# CM5_GPIO.net
KiCad netlist of a schematic drawn in Altium Designer
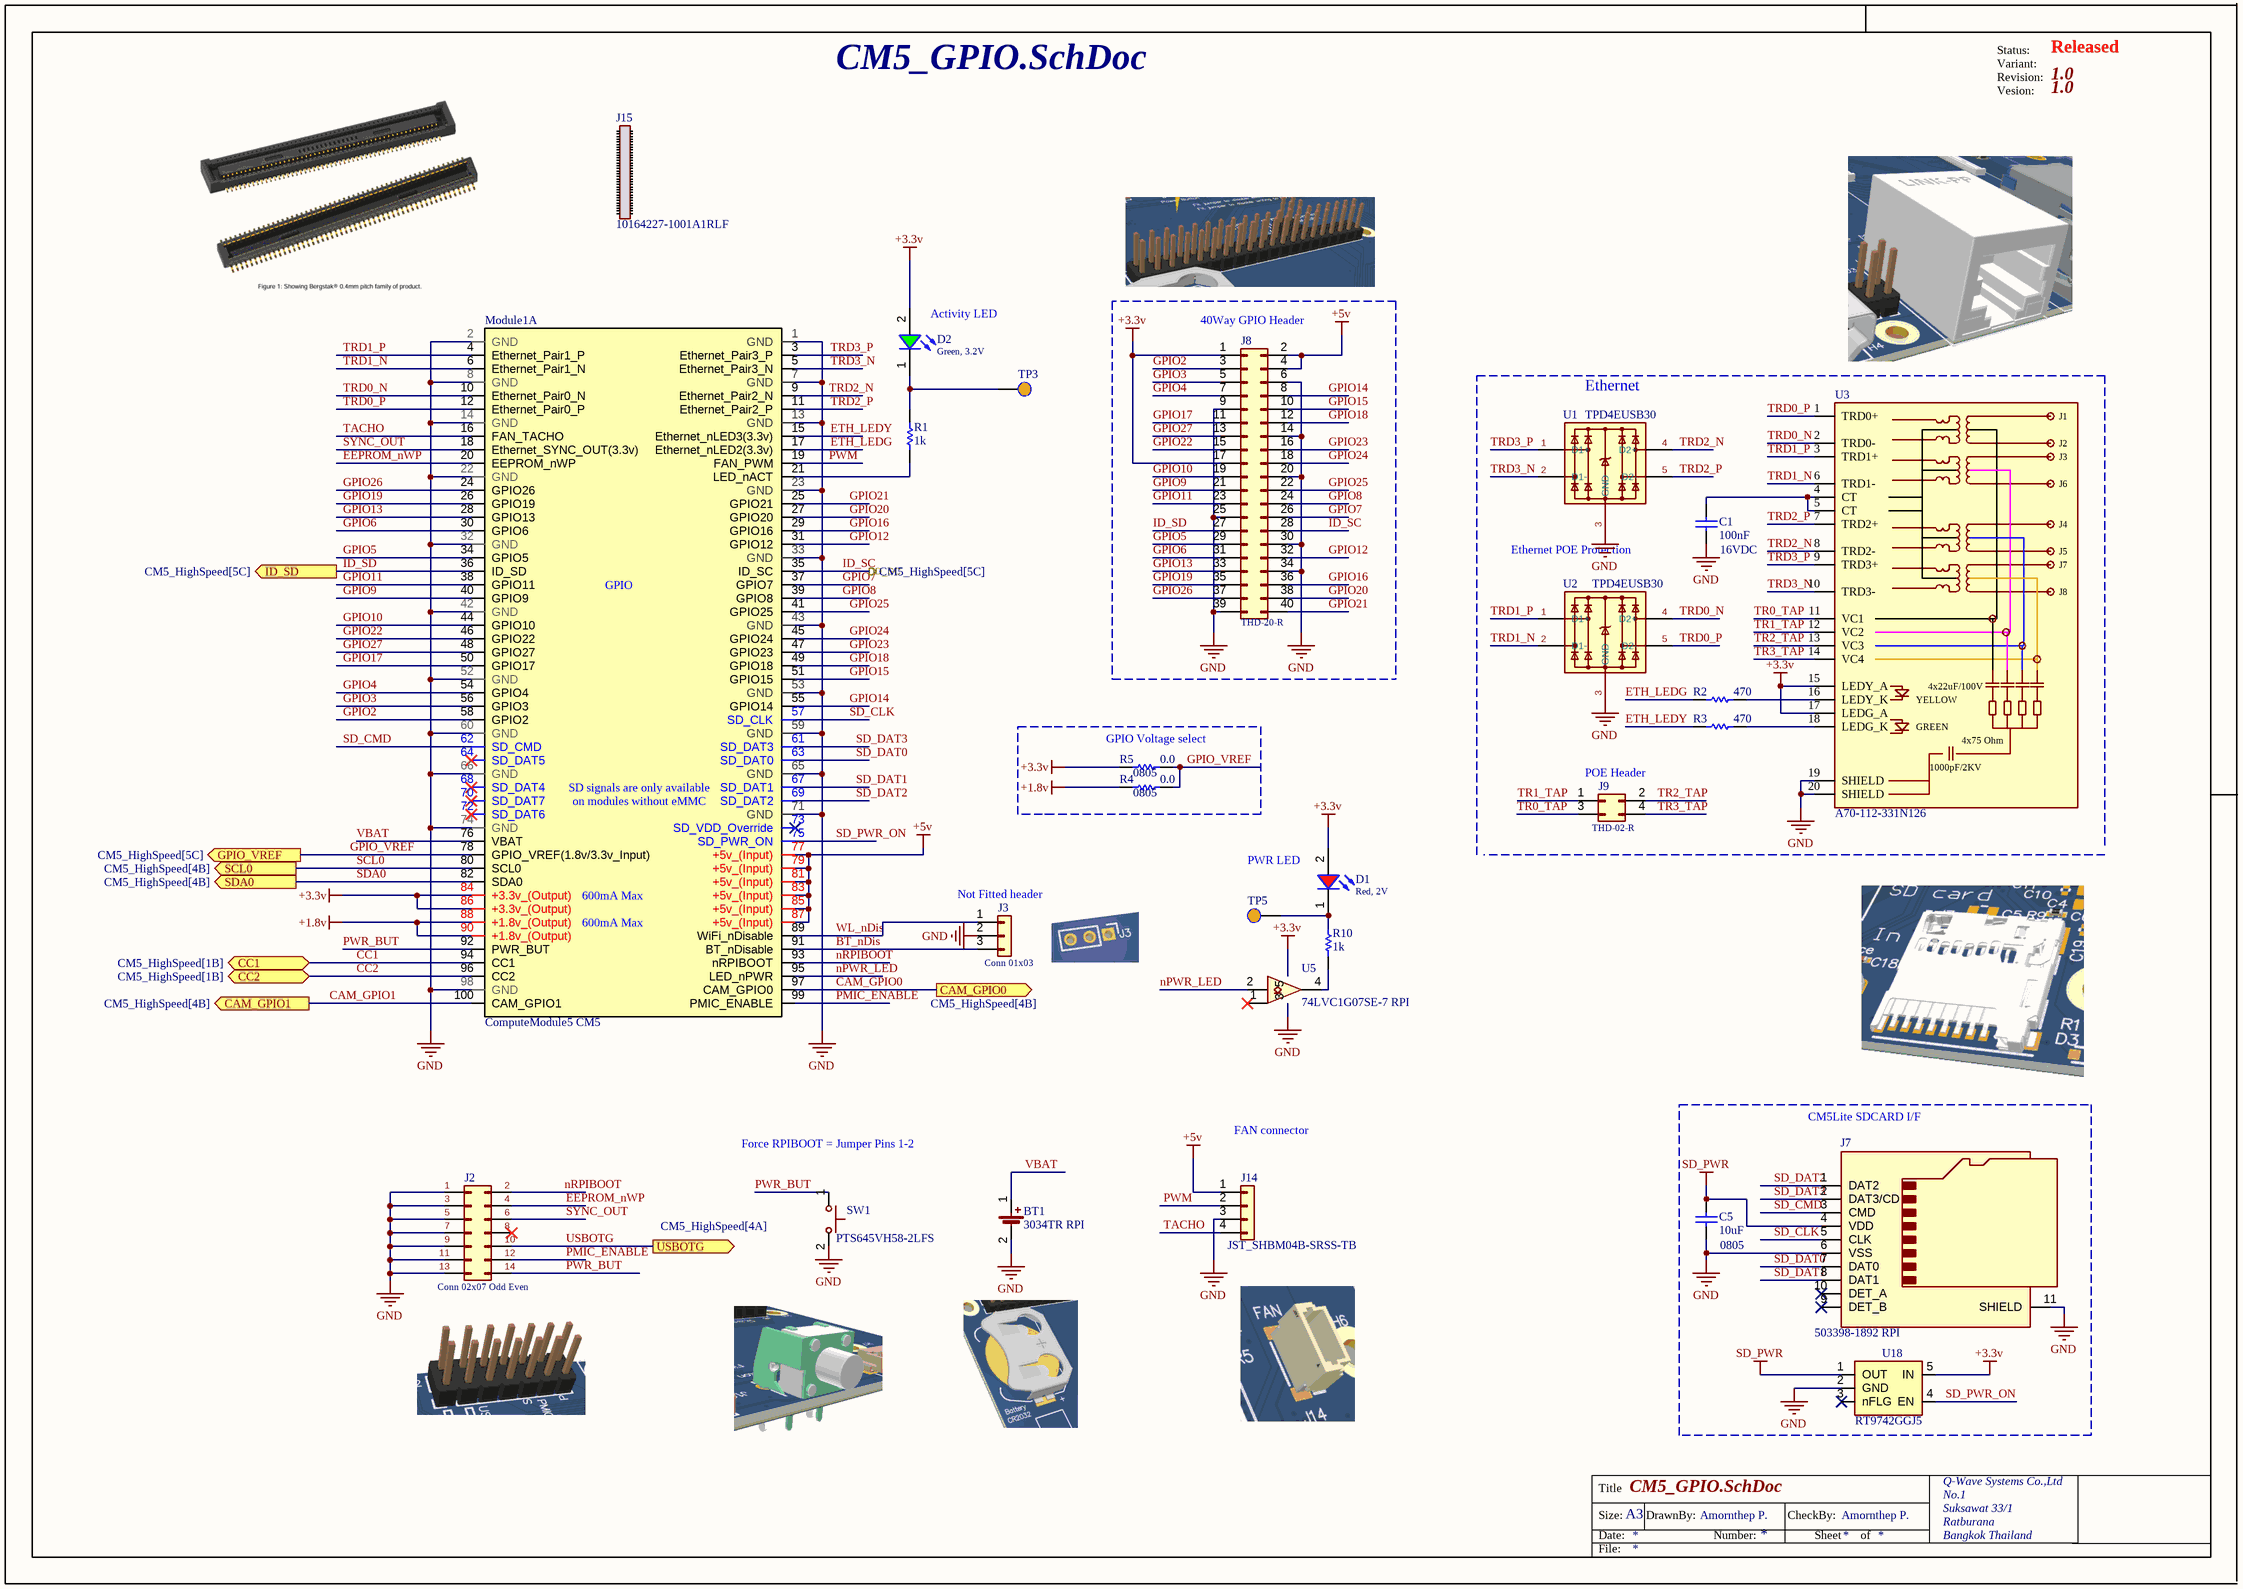
[diagram p0: CM5_GPIO.SchDoc]

(export (version "E")
  (design (tool "Eeschema 10.0.6"))
  (components
    (comp (ref "BT1")
      (value "3034TR RPI")
      (footprint "3034TR RPI")
      (description "Coin Cell Battery Holders COIN CELL RETAINER T APE/REEL 500PC")
      (libsource (lib "Q-WAVE SYSTEMS CO") (part "3034TR RPI"))
    )
    (comp (ref "C1")
      (value "100nF")
      (footprint "WCAP-CSGP_0402_H=0.5mm")
      (description "WCAP-CSGP Multilayer Ceramic Chip Capacitor, General Purpose, size 0402, X5R, 100nF, 16V")
      (fields
        (field (name "MANUFACTURER PART NUMBER") "885012105016")
        (field (name "MANUFACTURER") "Wurth Elektronik")
        (field (name "RATED VOLTAGE") "16VDC")
      )
      (libsource (lib "") (part "Symbol_1"))
    )
    (comp (ref "C5")
      (value "10uF")
      (footprint "WCAP-CSGP_0805_H=1.25mm")
      (description "WCAP-CSGP Multilayer Ceramic Chip Capacitor, General Purpose, size 0805, X5R, 10uF, 16V")
      (fields
        (field (name "MANUFACTURER") "Wurth Elektronik")
        (field (name "MANUFACTURER PART NUMBER") "885012107014")
        (field (name "SIZE") "0805")
      )
      (libsource (lib "") (part "Symbol_1"))
    )
    (comp (ref "D1")
      (value "Red, 2V")
      (footprint "WL-SMCW_0603_H=0.7mm_Red")
      (description "WL-SMCW SMT Mono-color Chip LED Waterclear, size 0603, Red, 2V, 140deg")
      (fields (field (name "PART NUMBER") "150060RS75000") (field (name "PUBLISHER") "Wurth Elektronik"))
      (libsource (lib "") (part "Symbol_2"))
    )
    (comp (ref "D2")
      (value "Green, 3.2V")
      (footprint "WL-SMCW_0603_H=0.7mm_Green")
      (description "WL-SMCW SMT Mono-color Chip LED Waterclear, size 0603, Green, 3.2V, 140deg")
      (fields (field (name "PART NUMBER") "150060GS75000") (field (name "PUBLISHER") "Wurth Elektronik"))
      (libsource (lib "") (part "Symbol_2"))
    )
    (comp (ref "J2")
      (value "Conn 02x07 Odd Even")
      (footprint "Conn 02x07 Odd Even")
      (description "PinHeader 2x07 P2.54mm Vertical")
      (fields
        (field (name "MANUFACTURER") "Wurth Elektronik")
        (field (name "MANUFACTURER PART NUMBER") "61301421121")
      )
      (libsource (lib "Q-WAVE SYSTEMS CO") (part "Conn 02x07 Odd Even"))
    )
    (comp (ref "J3")
      (value "Conn 01x03")
      (footprint "Conn 01x03")
      (description "PinHeader_1x03_P2.54mm_Vertical")
      (fields
        (field (name "MANUFACTURER") "Wurth Elektronik")
        (field (name "MANUFACTURER PART NUMBER") "61300311121")
      )
      (libsource (lib "Q-WAVE SYSTEMS CO") (part "Conn 01x03"))
    )
    (comp (ref "J7")
      (value "503398-1892 RPI")
      (footprint "503398-1892 RPI")
      (libsource (lib "Q-WAVE SYSTEMS CO") (part "503398-1892 RPI"))
    )
    (comp (ref "J8")
      (value "THD-20-R")
      (footprint "THD-20-R")
      (description "Through hole straight pin header, 2x20, 2.54mm pitch, double rows")
      (fields
        (field (name "MANUFACTURER PART NUMBER") "61304021121")
        (field (name "MANUFACTURER") "Wurth Elektronik")
      )
      (libsource (lib "Q-WAVE SYSTEMS CO") (part "THD-20-R"))
    )
    (comp (ref "J9")
      (value "THD-02-R")
      (footprint "THD-02-R")
      (description "PinHeader 2x02 P2.54mm Vertical")
      (fields
        (field (name "MANUFACTURER") "Wurth Elektronik")
        (field (name "MANUFACTURER PART NUMBER") "61300421121")
      )
      (libsource (lib "Q-WAVE SYSTEMS CO") (part "THD-02-R"))
    )
    (comp (ref "J14")
      (value "JST_SHBM04B-SRSS-TB")
      (footprint "JST_SHBM04B-SRSS-TB")
      (description "Board Connector, 4 Contact(s), 1 Row(s), Male, Straight, Surface Mount Terminal")
      (libsource (lib "Q-WAVE SYSTEMS CO") (part "JST_SHBM04B-SRSS-TB"))
    )
    (comp (ref "J15")
      (value "10164227-1001A1RLF")
      (footprint "CM5-BergStak-10164227")
      (description "CM5 1.5mm Height 0.4MM Btb, 100P, Receptacle, 1.5MM Stack Height")
      (libsource (lib "Q-WAVE SYSTEMS CO") (part "10164227-1001A1RLF"))
    )
    (comp (ref "Module1")
      (value "ComputeModule5 CM5")
      (footprint "ComputeModule5-CM5")
      (description "Raspberry Pi Compute Module 5")
      (libsource (lib "Q-WAVE SYSTEMS CO") (part "ComputeModule5-CM5"))
    )
    (comp (ref "R1")
      (value "1k")
      (footprint "SMD-0402-RES")
      (description "RES SMD 1K OHM 1% 1/10W 0402")
      (fields
        (field (name "MANUFACTURER") "Panasonic Electronic Components")
        (field (name "TOLERANCE") "±1%")
      )
      (libsource (lib "Q-WAVE SYSTEMS CO") (part "resistor"))
    )
    (comp (ref "R2")
      (value "470")
      (footprint "SMD-0402-RES")
      (description "RES SMD 470 OHM 1% 1/10W 0402")
      (fields (field (name "PART NUMBER") "ERJ-2RKF4700X") (field (name "DIGI-KEY PART NUMBER") "P470LCT-ND"))
      (libsource (lib "Q-WAVE SYSTEMS CO") (part "resistor"))
    )
    (comp (ref "R3")
      (value "470")
      (footprint "SMD-0402-RES")
      (description "RES SMD 470 OHM 1% 1/10W 0402")
      (fields (field (name "PART NUMBER") "ERJ-2RKF4700X") (field (name "DIGI-KEY PART NUMBER") "P470LCT-ND"))
      (libsource (lib "Q-WAVE SYSTEMS CO") (part "resistor"))
    )
    (comp (ref "R4")
      (value "0.0")
      (footprint "SMD-0805-RES")
      (description "RES SMD 0.0 OHM JUMPER 1/8W 0805")
      (fields
        (field (name "TOLERANCE") "Jumper")
        (field (name "PART NUMBER") "ERJ-6GEY0R00V")
        (field (name "SUPPLIER DEVICE PACKAGE") "0805")
      )
      (libsource (lib "Q-WAVE SYSTEMS CO") (part "Symbol"))
    )
    (comp (ref "R5")
      (value "0.0")
      (footprint "SMD-0805-RES")
      (description "RES SMD 0.0 OHM JUMPER 1/8W 0805")
      (fields
        (field (name "TOLERANCE") "Jumper")
        (field (name "PART NUMBER") "ERJ-6GEY0R00V")
        (field (name "SUPPLIER DEVICE PACKAGE") "0805")
      )
      (libsource (lib "Q-WAVE SYSTEMS CO") (part "Symbol"))
    )
    (comp (ref "R10")
      (value "1k")
      (footprint "SMD-0402-RES")
      (description "RES SMD 1K OHM 1% 1/10W 0402")
      (fields
        (field (name "MANUFACTURER") "Panasonic Electronic Components")
        (field (name "TOLERANCE") "±1%")
      )
      (libsource (lib "Q-WAVE SYSTEMS CO") (part "resistor"))
    )
    (comp (ref "SW1")
      (value "PTS645VH58-2LFS")
      (footprint "PTS645VH58-2LFS")
      (description "PTS645 Series Compact 6 x 6 mm SPST 2 N Through Hole Tactile Switch")
      (libsource (lib "Q-WAVE SYSTEMS CO") (part "PTS645VH58-2LFS"))
    )
    (comp (ref "TP3")
      (value "TEST_POINT 1")
      (footprint "TEST_POINT 1")
      (description "Test Point SMT PAD")
      (libsource (lib "Q-WAVE SYSTEMS CO") (part "TEST_POINT 1"))
    )
    (comp (ref "TP5")
      (value "TEST_POINT 1")
      (footprint "TEST_POINT 1")
      (description "Test Point SMT PAD")
      (libsource (lib "Q-WAVE SYSTEMS CO") (part "TEST_POINT 1"))
    )
    (comp (ref "U1")
      (value "TPD4EUSB30")
      (footprint "TPD4EUSB30")
      (libsource (lib "Q-WAVE SYSTEMS CO") (part "TPD4EUSB30"))
    )
    (comp (ref "U2")
      (value "TPD4EUSB30")
      (footprint "TPD4EUSB30")
      (libsource (lib "Q-WAVE SYSTEMS CO") (part "TPD4EUSB30"))
    )
    (comp (ref "U3")
      (value "A70-112-331N126")
      (footprint "A70-112-331N126")
      (libsource (lib "Q-WAVE SYSTEMS CO") (part "A70-112-331N126"))
    )
    (comp (ref "U5")
      (value "74LVC1G07SE-7 RPI")
      (footprint "74LVC1G07SE-7 RPI")
      (description "74LVC Series 5.5 V Surface Mount Single Buffer with Open Drain Output - SOT-353")
      (libsource (lib "Q-WAVE SYSTEMS CO") (part "74LVC1G07SE-7 RPI"))
    )
    (comp (ref "U18")
      (value "RT9742GGJ5")
      (footprint "FP-RT9742GGJ5-IPC_A")
      (description "IC Pwr Swtch N-chan 1: 1 TSOT23-5")
      (libsource (lib "Q-WAVE SYSTEMS CO") (part "RT9742GGJ5"))
    )
  )
  (nets
    (net (code "1") (name "+1.8v") (class "Default")
      (node (ref "Module1") (pin "88") (pinfunction "+1.8v_(Output)_88") (pintype "passive"))
      (node (ref "Module1") (pin "90") (pinfunction "+1.8v_(Output)_90") (pintype "passive"))
      (node (ref "R4") (pin "1") (pinfunction "1_1") (pintype "passive"))
    )
    (net (code "2") (name "+3.3v") (class "Default")
      (node (ref "D1") (pin "2") (pinfunction "A_2") (pintype "passive"))
      (node (ref "D2") (pin "2") (pinfunction "A_2") (pintype "passive"))
      (node (ref "J8") (pin "1") (pinfunction "Pin_1_1") (pintype "passive"))
      (node (ref "J8") (pin "17") (pinfunction "Pin_17_17") (pintype "passive"))
      (node (ref "Module1") (pin "84") (pinfunction "+3.3v_(Output)_84") (pintype "passive"))
      (node (ref "Module1") (pin "86") (pinfunction "+3.3v_(Output)_86") (pintype "passive"))
      (node (ref "R5") (pin "1") (pinfunction "1_1") (pintype "passive"))
      (node (ref "U18") (pin "5") (pinfunction "IN_5") (pintype "passive"))
      (node (ref "U3") (pin "15") (pinfunction "LEDY_A_15") (pintype "passive"))
      (node (ref "U3") (pin "17") (pinfunction "LEDG_A_17") (pintype "passive"))
      (node (ref "U5") (pin "5") (pinfunction "VCC_5") (pintype "passive"))
    )
    (net (code "3") (name "+5v") (class "Default")
      (node (ref "J14") (pin "1") (pinfunction "Pin_1_1") (pintype "passive"))
      (node (ref "J8") (pin "2") (pinfunction "Pin_2_2") (pintype "passive"))
      (node (ref "J8") (pin "4") (pinfunction "Pin_4_4") (pintype "passive"))
      (node (ref "Module1") (pin "77") (pinfunction "+5v_(Input)_77") (pintype "passive"))
      (node (ref "Module1") (pin "79") (pinfunction "+5v_(Input)_79") (pintype "passive"))
      (node (ref "Module1") (pin "81") (pinfunction "+5v_(Input)_81") (pintype "passive"))
      (node (ref "Module1") (pin "83") (pinfunction "+5v_(Input)_83") (pintype "passive"))
      (node (ref "Module1") (pin "85") (pinfunction "+5v_(Input)_85") (pintype "passive"))
      (node (ref "Module1") (pin "87") (pinfunction "+5v_(Input)_87") (pintype "passive"))
    )
    (net (code "4") (name "/BT_nDis") (class "Default")
      (node (ref "J3") (pin "3") (pinfunction "Pin_3_3") (pintype "passive"))
      (node (ref "Module1") (pin "91") (pinfunction "BT_nDisable_91") (pintype "passive"))
    )
    (net (code "5") (name "/CAM_GPIO0") (class "Default")
      (node (ref "Module1") (pin "97") (pinfunction "CAM_GPIO0_97") (pintype "passive"))
    )
    (net (code "6") (name "/CAM_GPIO1") (class "Default")
      (node (ref "Module1") (pin "100") (pinfunction "CAM_GPIO1_100") (pintype "passive"))
    )
    (net (code "7") (name "/CC1") (class "Default")
      (node (ref "Module1") (pin "94") (pinfunction "CC1_94") (pintype "passive"))
    )
    (net (code "8") (name "/CC2") (class "Default")
      (node (ref "Module1") (pin "96") (pinfunction "CC2_96") (pintype "passive"))
    )
    (net (code "9") (name "/EEPROM_nWP") (class "Default")
      (node (ref "J2") (pin "4") (pinfunction "Pin_4_4") (pintype "passive"))
      (node (ref "Module1") (pin "20") (pinfunction "EEPROM_nWP_20") (pintype "passive"))
    )
    (net (code "10") (name "/ETH_LEDG") (class "Default")
      (node (ref "Module1") (pin "17") (pinfunction "Ethernet_nLED2(3.3v)_17") (pintype "passive"))
      (node (ref "R2") (pin "1") (pinfunction "1_1") (pintype "passive"))
    )
    (net (code "11") (name "/ETH_LEDY") (class "Default")
      (node (ref "Module1") (pin "15") (pinfunction "Ethernet_nLED3(3.3v)_15") (pintype "passive"))
      (node (ref "R3") (pin "1") (pinfunction "1_1") (pintype "passive"))
    )
    (net (code "12") (name "/GPIO2") (class "Default")
      (node (ref "J8") (pin "3") (pinfunction "Pin_3_3") (pintype "passive"))
      (node (ref "Module1") (pin "58") (pinfunction "GPIO2_58") (pintype "passive"))
    )
    (net (code "13") (name "/GPIO3") (class "Default")
      (node (ref "J8") (pin "5") (pinfunction "Pin_5_5") (pintype "passive"))
      (node (ref "Module1") (pin "56") (pinfunction "GPIO3_56") (pintype "passive"))
    )
    (net (code "14") (name "/GPIO4") (class "Default")
      (node (ref "J8") (pin "7") (pinfunction "Pin_7_7") (pintype "passive"))
      (node (ref "Module1") (pin "54") (pinfunction "GPIO4_54") (pintype "passive"))
    )
    (net (code "15") (name "/GPIO5") (class "Default")
      (node (ref "J8") (pin "29") (pinfunction "Pin_29_29") (pintype "passive"))
      (node (ref "Module1") (pin "34") (pinfunction "GPIO5_34") (pintype "passive"))
    )
    (net (code "16") (name "/GPIO6") (class "Default")
      (node (ref "J8") (pin "31") (pinfunction "Pin_31_31") (pintype "passive"))
      (node (ref "Module1") (pin "30") (pinfunction "GPIO6_30") (pintype "passive"))
    )
    (net (code "17") (name "/GPIO7") (class "Default")
      (node (ref "J8") (pin "26") (pinfunction "Pin_26_26") (pintype "passive"))
      (node (ref "Module1") (pin "37") (pinfunction "GPIO7_37") (pintype "passive"))
    )
    (net (code "18") (name "/GPIO8") (class "Default")
      (node (ref "J8") (pin "24") (pinfunction "Pin_24_24") (pintype "passive"))
      (node (ref "Module1") (pin "39") (pinfunction "GPIO8_39") (pintype "passive"))
    )
    (net (code "19") (name "/GPIO9") (class "Default")
      (node (ref "J8") (pin "21") (pinfunction "Pin_21_21") (pintype "passive"))
      (node (ref "Module1") (pin "40") (pinfunction "GPIO9_40") (pintype "passive"))
    )
    (net (code "20") (name "/GPIO10") (class "Default")
      (node (ref "J8") (pin "19") (pinfunction "Pin_19_19") (pintype "passive"))
      (node (ref "Module1") (pin "44") (pinfunction "GPIO10_44") (pintype "passive"))
    )
    (net (code "21") (name "/GPIO11") (class "Default")
      (node (ref "J8") (pin "23") (pinfunction "Pin_23_23") (pintype "passive"))
      (node (ref "Module1") (pin "38") (pinfunction "GPIO11_38") (pintype "passive"))
    )
    (net (code "22") (name "/GPIO12") (class "Default")
      (node (ref "J8") (pin "32") (pinfunction "Pin_32_32") (pintype "passive"))
      (node (ref "Module1") (pin "31") (pinfunction "GPIO12_31") (pintype "passive"))
    )
    (net (code "23") (name "/GPIO13") (class "Default")
      (node (ref "J8") (pin "33") (pinfunction "Pin_33_33") (pintype "passive"))
      (node (ref "Module1") (pin "28") (pinfunction "GPIO13_28") (pintype "passive"))
    )
    (net (code "24") (name "/GPIO14") (class "Default")
      (node (ref "J8") (pin "8") (pinfunction "Pin_8_8") (pintype "passive"))
      (node (ref "Module1") (pin "55") (pinfunction "GPIO14_55") (pintype "passive"))
    )
    (net (code "25") (name "/GPIO15") (class "Default")
      (node (ref "J8") (pin "10") (pinfunction "Pin_10_10") (pintype "passive"))
      (node (ref "Module1") (pin "51") (pinfunction "GPIO15_51") (pintype "passive"))
    )
    (net (code "26") (name "/GPIO16") (class "Default")
      (node (ref "J8") (pin "36") (pinfunction "Pin_36_36") (pintype "passive"))
      (node (ref "Module1") (pin "29") (pinfunction "GPIO16_29") (pintype "passive"))
    )
    (net (code "27") (name "/GPIO17") (class "Default")
      (node (ref "J8") (pin "11") (pinfunction "Pin_11_11") (pintype "passive"))
      (node (ref "Module1") (pin "50") (pinfunction "GPIO17_50") (pintype "passive"))
    )
    (net (code "28") (name "/GPIO18") (class "Default")
      (node (ref "J8") (pin "12") (pinfunction "Pin_12_12") (pintype "passive"))
      (node (ref "Module1") (pin "49") (pinfunction "GPIO18_49") (pintype "passive"))
    )
    (net (code "29") (name "/GPIO19") (class "Default")
      (node (ref "J8") (pin "35") (pinfunction "Pin_35_35") (pintype "passive"))
      (node (ref "Module1") (pin "26") (pinfunction "GPIO19_26") (pintype "passive"))
    )
    (net (code "30") (name "/GPIO20") (class "Default")
      (node (ref "J8") (pin "38") (pinfunction "Pin_38_38") (pintype "passive"))
      (node (ref "Module1") (pin "27") (pinfunction "GPIO20_27") (pintype "passive"))
    )
    (net (code "31") (name "/GPIO21") (class "Default")
      (node (ref "J8") (pin "40") (pinfunction "Pin_40_40") (pintype "passive"))
      (node (ref "Module1") (pin "25") (pinfunction "GPIO21_25") (pintype "passive"))
    )
    (net (code "32") (name "/GPIO22") (class "Default")
      (node (ref "J8") (pin "15") (pinfunction "Pin_15_15") (pintype "passive"))
      (node (ref "Module1") (pin "46") (pinfunction "GPIO22_46") (pintype "passive"))
    )
    (net (code "33") (name "/GPIO23") (class "Default")
      (node (ref "J8") (pin "16") (pinfunction "Pin_16_16") (pintype "passive"))
      (node (ref "Module1") (pin "47") (pinfunction "GPIO23_47") (pintype "passive"))
    )
    (net (code "34") (name "/GPIO24") (class "Default")
      (node (ref "J8") (pin "18") (pinfunction "Pin_18_18") (pintype "passive"))
      (node (ref "Module1") (pin "45") (pinfunction "GPIO24_45") (pintype "passive"))
    )
    (net (code "35") (name "/GPIO25") (class "Default")
      (node (ref "J8") (pin "22") (pinfunction "Pin_22_22") (pintype "passive"))
      (node (ref "Module1") (pin "41") (pinfunction "GPIO25_41") (pintype "passive"))
    )
    (net (code "36") (name "/GPIO26") (class "Default")
      (node (ref "J8") (pin "37") (pinfunction "Pin_37_37") (pintype "passive"))
      (node (ref "Module1") (pin "24") (pinfunction "GPIO26_24") (pintype "passive"))
    )
    (net (code "37") (name "/GPIO27") (class "Default")
      (node (ref "J8") (pin "13") (pinfunction "Pin_13_13") (pintype "passive"))
      (node (ref "Module1") (pin "48") (pinfunction "GPIO27_48") (pintype "passive"))
    )
    (net (code "38") (name "/GPIO_VREF") (class "Default")
      (node (ref "Module1") (pin "78") (pinfunction "GPIO_VREF(1.8v/3.3v_Input)_78") (pintype "passive"))
      (node (ref "R4") (pin "2") (pinfunction "2_2") (pintype "passive"))
      (node (ref "R5") (pin "2") (pinfunction "2_2") (pintype "passive"))
    )
    (net (code "39") (name "/ID_SC") (class "Default")
      (node (ref "J8") (pin "28") (pinfunction "Pin_28_28") (pintype "passive"))
      (node (ref "Module1") (pin "35") (pinfunction "ID_SC_35") (pintype "passive"))
    )
    (net (code "40") (name "/ID_SD") (class "Default")
      (node (ref "J8") (pin "27") (pinfunction "Pin_27_27") (pintype "passive"))
      (node (ref "Module1") (pin "36") (pinfunction "ID_SD_36") (pintype "passive"))
    )
    (net (code "41") (name "/PMIC_ENABLE") (class "Default")
      (node (ref "J2") (pin "12") (pinfunction "Pin_12_12") (pintype "passive"))
      (node (ref "Module1") (pin "99") (pinfunction "PMIC_ENABLE_99") (pintype "passive"))
    )
    (net (code "42") (name "/PWM") (class "Default")
      (node (ref "J14") (pin "2") (pinfunction "Pin_2_2") (pintype "passive"))
      (node (ref "Module1") (pin "19") (pinfunction "FAN_PWM_19") (pintype "passive"))
    )
    (net (code "43") (name "/PWR_BUT") (class "Default")
      (node (ref "J2") (pin "14") (pinfunction "Pin_14_14") (pintype "passive"))
      (node (ref "Module1") (pin "92") (pinfunction "PWR_BUT_92") (pintype "passive"))
      (node (ref "SW1") (pin "1") (pinfunction "1_1") (pintype "passive"))
    )
    (net (code "44") (name "/SCL0") (class "Default")
      (node (ref "Module1") (pin "80") (pinfunction "SCL0_80") (pintype "passive"))
    )
    (net (code "45") (name "/SDA0") (class "Default")
      (node (ref "Module1") (pin "82") (pinfunction "SDA0_82") (pintype "passive"))
    )
    (net (code "46") (name "/SD_CLK") (class "Default")
      (node (ref "J7") (pin "5") (pinfunction "CLK_5") (pintype "passive"))
      (node (ref "Module1") (pin "57") (pinfunction "SD_CLK_57") (pintype "passive"))
    )
    (net (code "47") (name "/SD_CMD") (class "Default")
      (node (ref "J7") (pin "3") (pinfunction "CMD_3") (pintype "passive"))
      (node (ref "Module1") (pin "62") (pinfunction "SD_CMD_62") (pintype "passive"))
    )
    (net (code "48") (name "/SD_DAT0") (class "Default")
      (node (ref "J7") (pin "7") (pinfunction "DAT0_7") (pintype "passive"))
      (node (ref "Module1") (pin "63") (pinfunction "SD_DAT0_63") (pintype "passive"))
    )
    (net (code "49") (name "/SD_DAT1") (class "Default")
      (node (ref "J7") (pin "8") (pinfunction "DAT1_8") (pintype "passive"))
      (node (ref "Module1") (pin "67") (pinfunction "SD_DAT1_67") (pintype "passive"))
    )
    (net (code "50") (name "/SD_DAT2") (class "Default")
      (node (ref "J7") (pin "1") (pinfunction "DAT2_1") (pintype "passive"))
      (node (ref "Module1") (pin "69") (pinfunction "SD_DAT2_69") (pintype "passive"))
    )
    (net (code "51") (name "/SD_DAT3") (class "Default")
      (node (ref "J7") (pin "2") (pinfunction "DAT3/CD_2") (pintype "passive"))
      (node (ref "Module1") (pin "61") (pinfunction "SD_DAT3_61") (pintype "passive"))
    )
    (net (code "52") (name "/SD_PWR_ON") (class "Default")
      (node (ref "Module1") (pin "75") (pinfunction "SD_PWR_ON_75") (pintype "passive"))
      (node (ref "U18") (pin "4") (pinfunction "EN_4") (pintype "passive"))
    )
    (net (code "53") (name "/SYNC_OUT") (class "Default")
      (node (ref "J2") (pin "6") (pinfunction "Pin_6_6") (pintype "passive"))
      (node (ref "Module1") (pin "18") (pinfunction "Ethernet_SYNC_OUT(3.3v)_18") (pintype "passive"))
    )
    (net (code "54") (name "/TACHO") (class "Default")
      (node (ref "J14") (pin "4") (pinfunction "Pin_4_4") (pintype "passive"))
      (node (ref "Module1") (pin "16") (pinfunction "FAN_TACHO_16") (pintype "passive"))
    )
    (net (code "55") (name "/TR0_TAP") (class "Default")
      (node (ref "J9") (pin "3") (pinfunction "Pin_3_3") (pintype "passive"))
      (node (ref "U3") (pin "11") (pinfunction "VC1_11") (pintype "passive"))
    )
    (net (code "56") (name "/TR1_TAP") (class "Default")
      (node (ref "J9") (pin "1") (pinfunction "Pin_1_1") (pintype "passive"))
      (node (ref "U3") (pin "12") (pinfunction "VC2_12") (pintype "passive"))
    )
    (net (code "57") (name "/TR2_TAP") (class "Default")
      (node (ref "J9") (pin "2") (pinfunction "Pin_2_2") (pintype "passive"))
      (node (ref "U3") (pin "13") (pinfunction "VC3_13") (pintype "passive"))
    )
    (net (code "58") (name "/TR3_TAP") (class "Default")
      (node (ref "J9") (pin "4") (pinfunction "Pin_4_4") (pintype "passive"))
      (node (ref "U3") (pin "14") (pinfunction "VC4_14") (pintype "passive"))
    )
    (net (code "59") (name "/TRD0_N") (class "Default")
      (node (ref "Module1") (pin "10") (pinfunction "Ethernet_Pair0_N_10") (pintype "passive"))
      (node (ref "U2") (pin "4") (pinfunction "D2+_4") (pintype "passive"))
      (node (ref "U3") (pin "2") (pinfunction "TRD0-_2") (pintype "passive"))
    )
    (net (code "60") (name "/TRD0_P") (class "Default")
      (node (ref "Module1") (pin "12") (pinfunction "Ethernet_Pair0_P_12") (pintype "passive"))
      (node (ref "U2") (pin "5") (pinfunction "D2-_5") (pintype "passive"))
      (node (ref "U3") (pin "1") (pinfunction "TRD0+_1") (pintype "passive"))
    )
    (net (code "61") (name "/TRD1_N") (class "Default")
      (node (ref "Module1") (pin "6") (pinfunction "Ethernet_Pair1_N_6") (pintype "passive"))
      (node (ref "U2") (pin "2") (pinfunction "D1-_2") (pintype "passive"))
      (node (ref "U3") (pin "6") (pinfunction "TRD1-_6") (pintype "passive"))
    )
    (net (code "62") (name "/TRD1_P") (class "Default")
      (node (ref "Module1") (pin "4") (pinfunction "Ethernet_Pair1_P_4") (pintype "passive"))
      (node (ref "U2") (pin "1") (pinfunction "D1+_1") (pintype "passive"))
      (node (ref "U3") (pin "3") (pinfunction "TRD1+_3") (pintype "passive"))
    )
    (net (code "63") (name "/TRD2_N") (class "Default")
      (node (ref "Module1") (pin "9") (pinfunction "Ethernet_Pair2_N_9") (pintype "passive"))
      (node (ref "U1") (pin "4") (pinfunction "D2+_4") (pintype "passive"))
      (node (ref "U3") (pin "8") (pinfunction "TRD2-_8") (pintype "passive"))
    )
    (net (code "64") (name "/TRD2_P") (class "Default")
      (node (ref "Module1") (pin "11") (pinfunction "Ethernet_Pair2_P_11") (pintype "passive"))
      (node (ref "U1") (pin "5") (pinfunction "D2-_5") (pintype "passive"))
      (node (ref "U3") (pin "7") (pinfunction "TRD2+_7") (pintype "passive"))
    )
    (net (code "65") (name "/TRD3_N") (class "Default")
      (node (ref "Module1") (pin "5") (pinfunction "Ethernet_Pair3_N_5") (pintype "passive"))
      (node (ref "U1") (pin "2") (pinfunction "D1-_2") (pintype "passive"))
      (node (ref "U3") (pin "10") (pinfunction "TRD3-_10") (pintype "passive"))
    )
    (net (code "66") (name "/TRD3_P") (class "Default")
      (node (ref "Module1") (pin "3") (pinfunction "Ethernet_Pair3_P_3") (pintype "passive"))
      (node (ref "U1") (pin "1") (pinfunction "D1+_1") (pintype "passive"))
      (node (ref "U3") (pin "9") (pinfunction "TRD3+_9") (pintype "passive"))
    )
    (net (code "67") (name "/USBOTG") (class "Default")
      (node (ref "J2") (pin "10") (pinfunction "Pin_10_10") (pintype "passive"))
    )
    (net (code "68") (name "/VBAT") (class "Default")
      (node (ref "BT1") (pin "1") (pinfunction "+_1") (pintype "passive"))
      (node (ref "Module1") (pin "76") (pinfunction "VBAT_76") (pintype "passive"))
    )
    (net (code "69") (name "/WL_nDis") (class "Default")
      (node (ref "J3") (pin "1") (pinfunction "Pin_1_1") (pintype "passive"))
      (node (ref "Module1") (pin "89") (pinfunction "WiFi_nDisable_89") (pintype "passive"))
    )
    (net (code "70") (name "/nPWR_LED") (class "Default")
      (node (ref "Module1") (pin "95") (pinfunction "LED_nPWR_95") (pintype "passive"))
      (node (ref "U5") (pin "2") (pinfunction "2_2") (pintype "passive"))
    )
    (net (code "71") (name "/nRPIBOOT") (class "Default")
      (node (ref "J2") (pin "2") (pinfunction "Pin_2_2") (pintype "passive"))
      (node (ref "Module1") (pin "93") (pinfunction "nRPIBOOT_93") (pintype "passive"))
    )
    (net (code "72") (name "GND") (class "Default")
      (node (ref "BT1") (pin "2") (pinfunction "-_2") (pintype "passive"))
      (node (ref "C1") (pin "1") (pinfunction "1_1") (pintype "passive"))
      (node (ref "C5") (pin "1") (pinfunction "1_1") (pintype "passive"))
      (node (ref "J14") (pin "3") (pinfunction "Pin_3_3") (pintype "passive"))
      (node (ref "J2") (pin "1") (pinfunction "Pin_1_1") (pintype "passive"))
      (node (ref "J2") (pin "11") (pinfunction "Pin_11_11") (pintype "passive"))
      (node (ref "J2") (pin "13") (pinfunction "Pin_13_13") (pintype "passive"))
      (node (ref "J2") (pin "3") (pinfunction "Pin_3_3") (pintype "passive"))
      (node (ref "J2") (pin "5") (pinfunction "Pin_5_5") (pintype "passive"))
      (node (ref "J2") (pin "7") (pinfunction "Pin_7_7") (pintype "passive"))
      (node (ref "J2") (pin "9") (pinfunction "Pin_9_9") (pintype "passive"))
      (node (ref "J3") (pin "2") (pinfunction "Pin_2_2") (pintype "passive"))
      (node (ref "J7") (pin "11") (pinfunction "SHIELD_11") (pintype "passive"))
      (node (ref "J7") (pin "6") (pinfunction "VSS_6") (pintype "passive"))
      (node (ref "J8") (pin "14") (pinfunction "Pin_14_14") (pintype "passive"))
      (node (ref "J8") (pin "20") (pinfunction "Pin_20_20") (pintype "passive"))
      (node (ref "J8") (pin "25") (pinfunction "Pin_25_25") (pintype "passive"))
      (node (ref "J8") (pin "30") (pinfunction "Pin_30_30") (pintype "passive"))
      (node (ref "J8") (pin "34") (pinfunction "Pin_34_34") (pintype "passive"))
      (node (ref "J8") (pin "39") (pinfunction "Pin_39_39") (pintype "passive"))
      (node (ref "J8") (pin "6") (pinfunction "Pin_6_6") (pintype "passive"))
      (node (ref "J8") (pin "9") (pinfunction "Pin_9_9") (pintype "passive"))
      (node (ref "Module1") (pin "1") (pinfunction "GND_1") (pintype "passive"))
      (node (ref "Module1") (pin "13") (pinfunction "GND_13") (pintype "passive"))
      (node (ref "Module1") (pin "14") (pinfunction "GND_14") (pintype "passive"))
      (node (ref "Module1") (pin "2") (pinfunction "GND_2") (pintype "passive"))
      (node (ref "Module1") (pin "22") (pinfunction "GND_22") (pintype "passive"))
      (node (ref "Module1") (pin "23") (pinfunction "GND_23") (pintype "passive"))
      (node (ref "Module1") (pin "32") (pinfunction "GND_32") (pintype "passive"))
      (node (ref "Module1") (pin "33") (pinfunction "GND_33") (pintype "passive"))
      (node (ref "Module1") (pin "42") (pinfunction "GND_42") (pintype "passive"))
      (node (ref "Module1") (pin "43") (pinfunction "GND_43") (pintype "passive"))
      (node (ref "Module1") (pin "52") (pinfunction "GND_52") (pintype "passive"))
      (node (ref "Module1") (pin "53") (pinfunction "GND_53") (pintype "passive"))
      (node (ref "Module1") (pin "59") (pinfunction "GND_59") (pintype "passive"))
      (node (ref "Module1") (pin "60") (pinfunction "GND_60") (pintype "passive"))
      (node (ref "Module1") (pin "65") (pinfunction "GND_65") (pintype "passive"))
      (node (ref "Module1") (pin "66") (pinfunction "GND_66") (pintype "passive"))
      (node (ref "Module1") (pin "7") (pinfunction "GND_7") (pintype "passive"))
      (node (ref "Module1") (pin "71") (pinfunction "GND_71") (pintype "passive"))
      (node (ref "Module1") (pin "74") (pinfunction "GND_74") (pintype "passive"))
      (node (ref "Module1") (pin "8") (pinfunction "GND_8") (pintype "passive"))
      (node (ref "Module1") (pin "98") (pinfunction "GND_98") (pintype "passive"))
      (node (ref "SW1") (pin "2") (pinfunction "2_2") (pintype "passive"))
      (node (ref "U1") (pin "3") (pinfunction "GND_3") (pintype "passive"))
      (node (ref "U18") (pin "2") (pinfunction "GND_2") (pintype "passive"))
      (node (ref "U2") (pin "3") (pinfunction "GND_3") (pintype "passive"))
      (node (ref "U3") (pin "19") (pinfunction "SHIELD_19") (pintype "passive"))
      (node (ref "U3") (pin "20") (pinfunction "SHIELD_20") (pintype "passive"))
      (node (ref "U5") (pin "3") (pinfunction "GND_3") (pintype "passive"))
    )
    (net (code "73") (name "Net-(C1-Pad2)") (class "Default")
      (node (ref "C1") (pin "2") (pinfunction "2_2") (pintype "passive"))
      (node (ref "U3") (pin "4") (pinfunction "CT_4") (pintype "passive"))
      (node (ref "U3") (pin "5") (pinfunction "CT_5") (pintype "passive"))
    )
    (net (code "74") (name "Net-(D1-K)") (class "Default")
      (node (ref "D1") (pin "1") (pinfunction "K_1") (pintype "passive"))
      (node (ref "R10") (pin "2") (pinfunction "2_2") (pintype "passive"))
      (node (ref "TP5") (pin "1") (pinfunction "1_1") (pintype "passive"))
    )
    (net (code "75") (name "Net-(D2-K)") (class "Default")
      (node (ref "D2") (pin "1") (pinfunction "K_1") (pintype "passive"))
      (node (ref "R1") (pin "2") (pinfunction "2_2") (pintype "passive"))
      (node (ref "TP3") (pin "1") (pinfunction "1_1") (pintype "passive"))
    )
    (net (code "76") (name "Net-(Module1A-LED_nACT)") (class "Default")
      (node (ref "Module1") (pin "21") (pinfunction "LED_nACT_21") (pintype "passive"))
      (node (ref "R1") (pin "1") (pinfunction "1_1") (pintype "passive"))
    )
    (net (code "77") (name "Net-(R10-Pad1)") (class "Default")
      (node (ref "R10") (pin "1") (pinfunction "1_1") (pintype "passive"))
      (node (ref "U5") (pin "4") (pinfunction "4_4") (pintype "passive"))
    )
    (net (code "78") (name "Net-(U3-LEDG_K)") (class "Default")
      (node (ref "R3") (pin "2") (pinfunction "2_2") (pintype "passive"))
      (node (ref "U3") (pin "18") (pinfunction "LEDG_K_18") (pintype "passive"))
    )
    (net (code "79") (name "Net-(U3-LEDY_K)") (class "Default")
      (node (ref "R2") (pin "2") (pinfunction "2_2") (pintype "passive"))
      (node (ref "U3") (pin "16") (pinfunction "LEDY_K_16") (pintype "passive"))
    )
    (net (code "80") (name "SD_PWR") (class "Default")
      (node (ref "C5") (pin "2") (pinfunction "2_2") (pintype "passive"))
      (node (ref "J7") (pin "4") (pinfunction "VDD_4") (pintype "passive"))
      (node (ref "U18") (pin "1") (pinfunction "OUT_1") (pintype "passive"))
    )
    (net (code "81") (name "unconnected-(J2-Pin_8-Pad8)") (class "Default")
      (node (ref "J2") (pin "8") (pinfunction "Pin_8_8") (pintype "passive+no_connect"))
    )
    (net (code "82") (name "unconnected-(J7-DET_A-Pad10)") (class "Default")
      (node (ref "J7") (pin "10") (pinfunction "DET_A_10") (pintype "passive+no_connect"))
    )
    (net (code "83") (name "unconnected-(J7-DET_B-Pad9)") (class "Default")
      (node (ref "J7") (pin "9") (pinfunction "DET_B_9") (pintype "passive+no_connect"))
    )
    (net (code "84") (name "unconnected-(Module1A-SD_DAT4-Pad68)") (class "Default")
      (node (ref "Module1") (pin "68") (pinfunction "SD_DAT4_68") (pintype "passive+no_connect"))
    )
    (net (code "85") (name "unconnected-(Module1A-SD_DAT5-Pad64)") (class "Default")
      (node (ref "Module1") (pin "64") (pinfunction "SD_DAT5_64") (pintype "passive+no_connect"))
    )
    (net (code "86") (name "unconnected-(Module1A-SD_DAT6-Pad72)") (class "Default")
      (node (ref "Module1") (pin "72") (pinfunction "SD_DAT6_72") (pintype "passive+no_connect"))
    )
    (net (code "87") (name "unconnected-(Module1A-SD_DAT7-Pad70)") (class "Default")
      (node (ref "Module1") (pin "70") (pinfunction "SD_DAT7_70") (pintype "passive+no_connect"))
    )
    (net (code "88") (name "unconnected-(Module1A-SD_VDD_Override-Pad73)") (class "Default")
      (node (ref "Module1") (pin "73") (pinfunction "SD_VDD_Override_73") (pintype "passive+no_connect"))
    )
    (net (code "89") (name "unconnected-(U5-nc-Pad1)") (class "Default")
      (node (ref "U5") (pin "1") (pinfunction "nc_1") (pintype "passive+no_connect"))
    )
    (net (code "90") (name "unconnected-(U18-nFLG-Pad3)") (class "Default")
      (node (ref "U18") (pin "3") (pinfunction "nFLG_3") (pintype "passive+no_connect"))
    )
  )
)
